# PBOARD.net
KiCad netlist of a schematic drawn in EAGLE
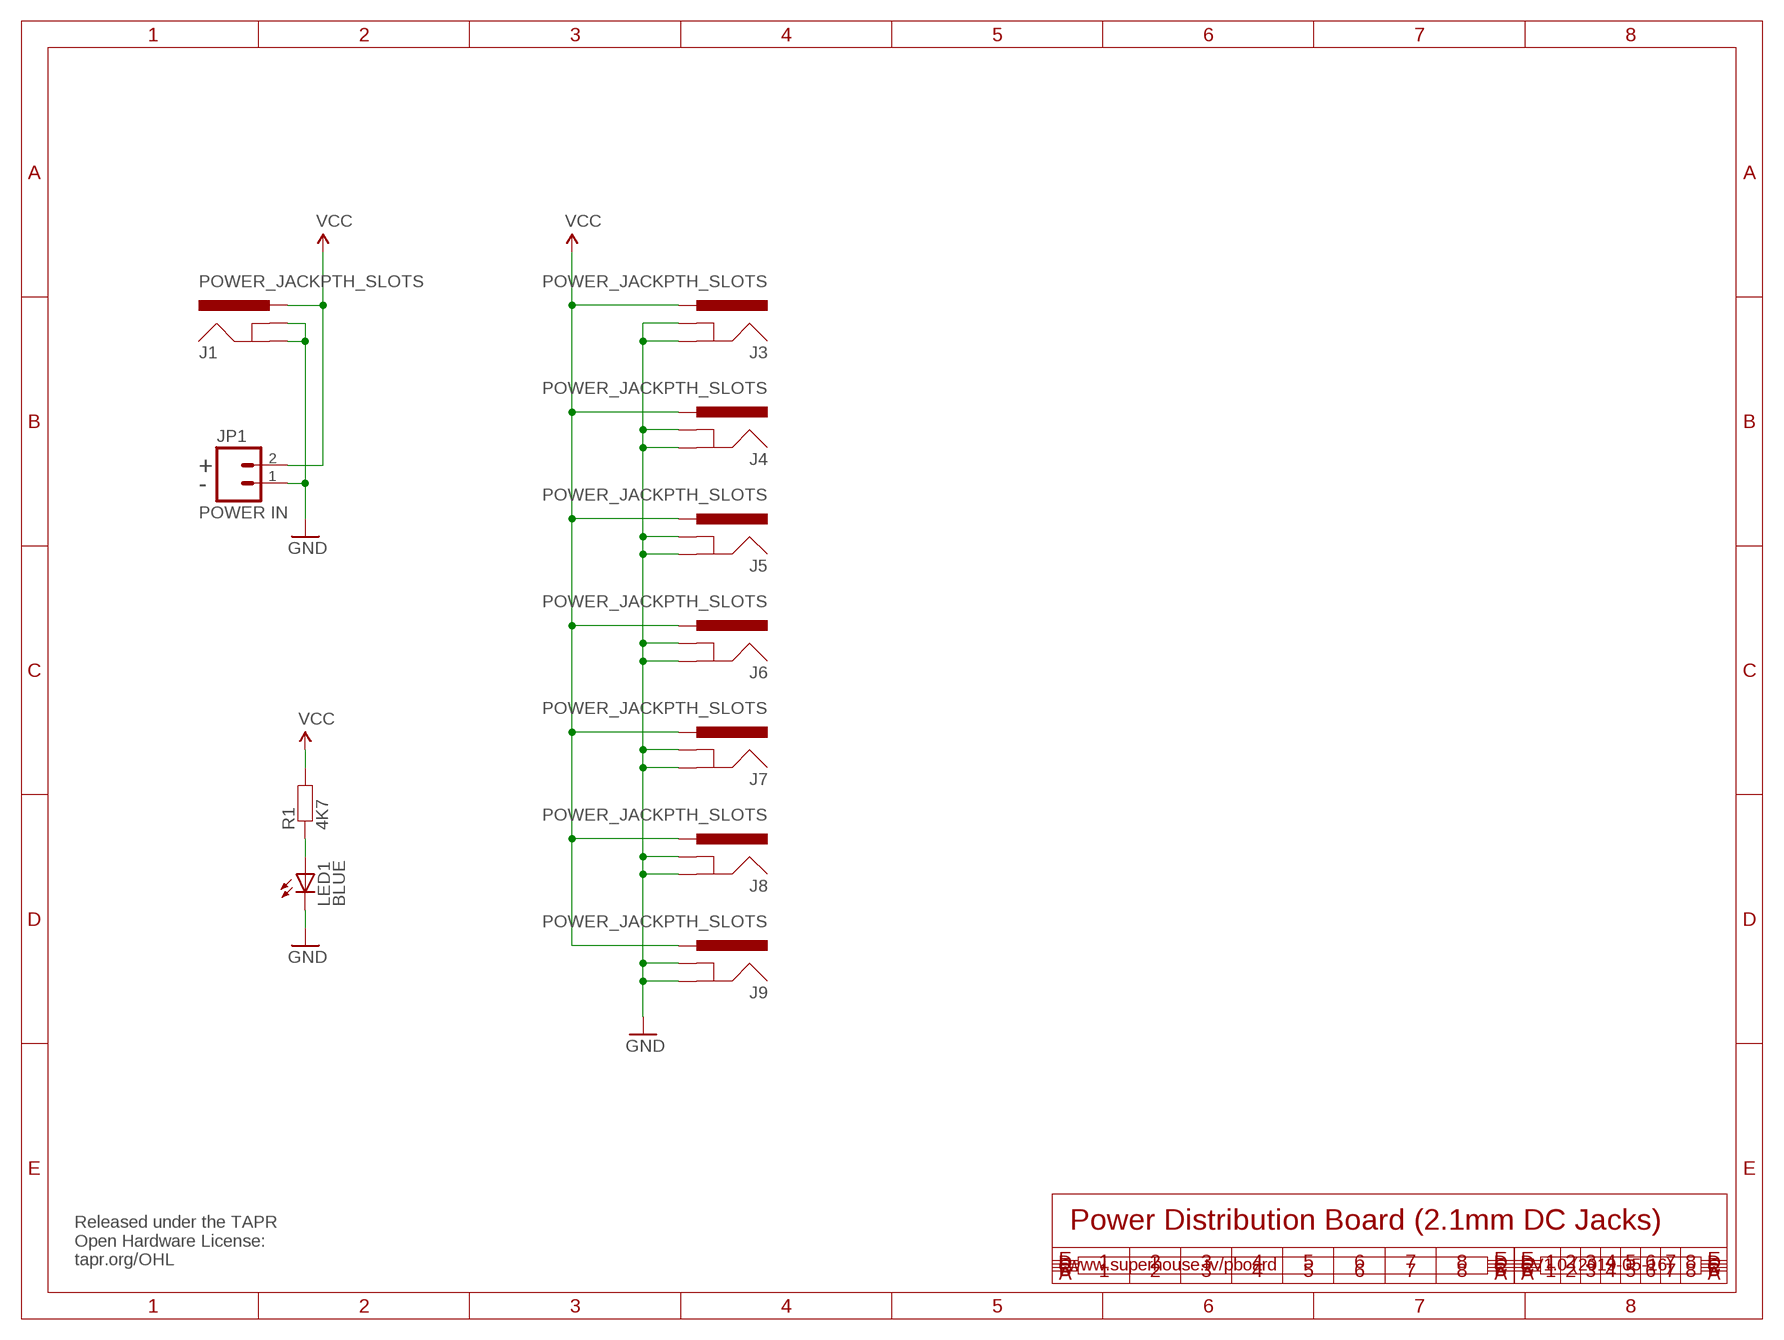
[diagram p0: schematic, sheet 1]

(export (version "E")
  (design (tool "Eeschema 10.0.6"))
  (components
    (comp (ref "J1")
      (value "POWER_JACKPTH_SLOTS")
      (footprint "eagle-import:POWER_JACK_PTH_SLOTS")
      (libsource (lib "eagle-import") (part "POWER_JACKPTH_SLOTS"))
    )
    (comp (ref "J3")
      (value "POWER_JACKPTH_SLOTS")
      (footprint "eagle-import:POWER_JACK_PTH_SLOTS")
      (libsource (lib "eagle-import") (part "POWER_JACKPTH_SLOTS"))
    )
    (comp (ref "J4")
      (value "POWER_JACKPTH_SLOTS")
      (footprint "eagle-import:POWER_JACK_PTH_SLOTS")
      (libsource (lib "eagle-import") (part "POWER_JACKPTH_SLOTS"))
    )
    (comp (ref "J5")
      (value "POWER_JACKPTH_SLOTS")
      (footprint "eagle-import:POWER_JACK_PTH_SLOTS")
      (libsource (lib "eagle-import") (part "POWER_JACKPTH_SLOTS"))
    )
    (comp (ref "J6")
      (value "POWER_JACKPTH_SLOTS")
      (footprint "eagle-import:POWER_JACK_PTH_SLOTS")
      (libsource (lib "eagle-import") (part "POWER_JACKPTH_SLOTS"))
    )
    (comp (ref "J7")
      (value "POWER_JACKPTH_SLOTS")
      (footprint "eagle-import:POWER_JACK_PTH_SLOTS")
      (libsource (lib "eagle-import") (part "POWER_JACKPTH_SLOTS"))
    )
    (comp (ref "J8")
      (value "POWER_JACKPTH_SLOTS")
      (footprint "eagle-import:POWER_JACK_PTH_SLOTS")
      (libsource (lib "eagle-import") (part "POWER_JACKPTH_SLOTS"))
    )
    (comp (ref "J9")
      (value "POWER_JACKPTH_SLOTS")
      (footprint "eagle-import:POWER_JACK_PTH_SLOTS")
      (libsource (lib "eagle-import") (part "POWER_JACKPTH_SLOTS"))
    )
    (comp (ref "JP1")
      (value "POWER IN")
      (footprint "eagle-import:SCREWTERMINAL-5MM-2")
      (libsource (lib "eagle-import") (part "M025MM"))
    )
    (comp (ref "LED1")
      (value "BLUE")
      (footprint "eagle-import:LED3MM")
      (libsource (lib "eagle-import") (part "LED3MM"))
    )
    (comp (ref "R1")
      (value "4K7")
      (footprint "eagle-import:AXIAL-0.3")
      (libsource (lib "eagle-import") (part "RESISTORPTH1"))
    )
  )
  (nets
    (net (code "1") (name "GND") (class "Default")
      (node (ref "J1") (pin "GND") (pinfunction "GND_GND") (pintype "bidirectional"))
      (node (ref "J1") (pin "GNDBREAK") (pinfunction "GNDBREAK_GNDBREAK") (pintype "bidirectional"))
      (node (ref "J3") (pin "GND") (pinfunction "GND_GND") (pintype "bidirectional"))
      (node (ref "J3") (pin "GNDBREAK") (pinfunction "GNDBREAK_GNDBREAK") (pintype "bidirectional"))
      (node (ref "J4") (pin "GND") (pinfunction "GND_GND") (pintype "bidirectional"))
      (node (ref "J4") (pin "GNDBREAK") (pinfunction "GNDBREAK_GNDBREAK") (pintype "bidirectional"))
      (node (ref "J5") (pin "GND") (pinfunction "GND_GND") (pintype "bidirectional"))
      (node (ref "J5") (pin "GNDBREAK") (pinfunction "GNDBREAK_GNDBREAK") (pintype "bidirectional"))
      (node (ref "J6") (pin "GND") (pinfunction "GND_GND") (pintype "bidirectional"))
      (node (ref "J6") (pin "GNDBREAK") (pinfunction "GNDBREAK_GNDBREAK") (pintype "bidirectional"))
      (node (ref "J7") (pin "GND") (pinfunction "GND_GND") (pintype "bidirectional"))
      (node (ref "J7") (pin "GNDBREAK") (pinfunction "GNDBREAK_GNDBREAK") (pintype "bidirectional"))
      (node (ref "J8") (pin "GND") (pinfunction "GND_GND") (pintype "bidirectional"))
      (node (ref "J8") (pin "GNDBREAK") (pinfunction "GNDBREAK_GNDBREAK") (pintype "bidirectional"))
      (node (ref "J9") (pin "GND") (pinfunction "GND_GND") (pintype "bidirectional"))
      (node (ref "J9") (pin "GNDBREAK") (pinfunction "GNDBREAK_GNDBREAK") (pintype "bidirectional"))
      (node (ref "JP1") (pin "1") (pinfunction "1_1") (pintype "passive"))
      (node (ref "LED1") (pin "K") (pinfunction "C_K") (pintype "passive"))
    )
    (net (code "2") (name "Net-(R1-1)") (class "Default")
      (node (ref "LED1") (pin "A") (pinfunction "A_A") (pintype "passive"))
      (node (ref "R1") (pin "P$1") (pinfunction "1_P$1") (pintype "passive"))
    )
    (net (code "3") (name "VCC") (class "Default")
      (node (ref "J1") (pin "PWR") (pinfunction "PWR_PWR") (pintype "bidirectional"))
      (node (ref "J3") (pin "PWR") (pinfunction "PWR_PWR") (pintype "bidirectional"))
      (node (ref "J4") (pin "PWR") (pinfunction "PWR_PWR") (pintype "bidirectional"))
      (node (ref "J5") (pin "PWR") (pinfunction "PWR_PWR") (pintype "bidirectional"))
      (node (ref "J6") (pin "PWR") (pinfunction "PWR_PWR") (pintype "bidirectional"))
      (node (ref "J7") (pin "PWR") (pinfunction "PWR_PWR") (pintype "bidirectional"))
      (node (ref "J8") (pin "PWR") (pinfunction "PWR_PWR") (pintype "bidirectional"))
      (node (ref "J9") (pin "PWR") (pinfunction "PWR_PWR") (pintype "bidirectional"))
      (node (ref "JP1") (pin "2") (pinfunction "2_2") (pintype "passive"))
      (node (ref "R1") (pin "P$2") (pinfunction "2_P$2") (pintype "passive"))
    )
  )
)
